# item_2223_Frontend.net
KiCad netlist of a schematic drawn in EAGLE
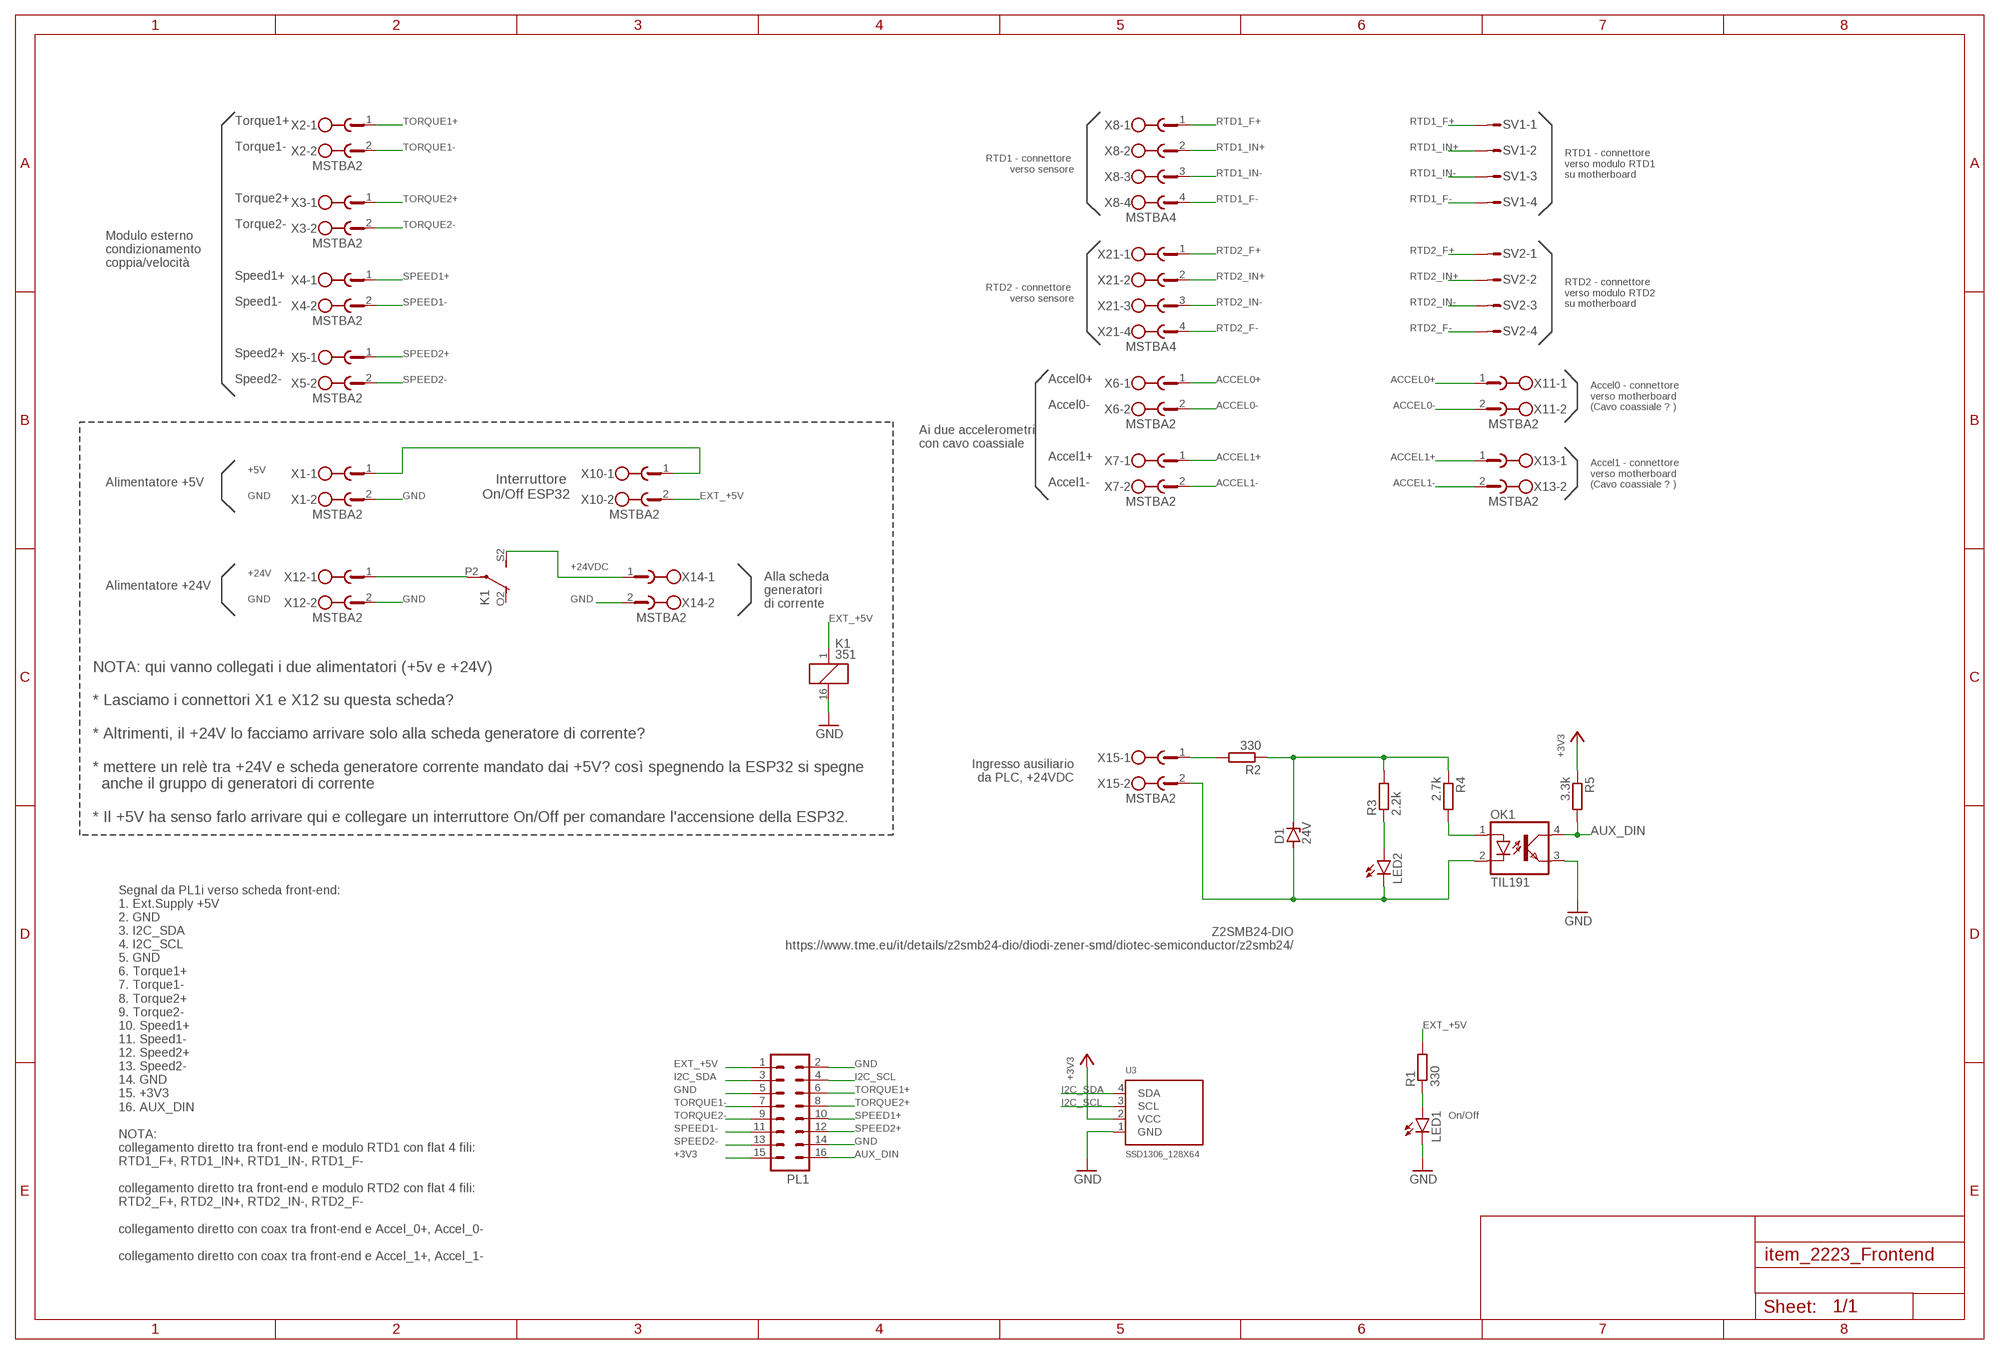
[diagram p0: schematic, sheet 1]

(export (version "E")
  (design (tool "Eeschema 10.0.6"))
  (components
    (comp (ref "D1")
      (value "24V")
      (footprint "eagle-import:SMB")
      (libsource (lib "eagle-import") (part "ZENER-DIODESMB"))
    )
    (comp (ref "K1")
      (value "351")
      (footprint "eagle-import:351")
      (libsource (lib "eagle-import") (part "351"))
    )
    (comp (ref "LED1")
      (value "LED5MM")
      (footprint "eagle-import:LED5MM")
      (libsource (lib "eagle-import") (part "LED5MM"))
    )
    (comp (ref "LED2")
      (value "LED5MM")
      (footprint "eagle-import:LED5MM")
      (libsource (lib "eagle-import") (part "LED5MM"))
    )
    (comp (ref "OK1")
      (value "TIL191")
      (footprint "eagle-import:DIL04")
      (libsource (lib "eagle-import") (part "TIL191"))
    )
    (comp (ref "PL1")
      (value "16H")
      (footprint "eagle-import:16H")
      (libsource (lib "eagle-import") (part "16H"))
    )
    (comp (ref "R1")
      (value "330")
      (footprint "eagle-import:R0805")
      (libsource (lib "eagle-import") (part "R-EU_R0805"))
    )
    (comp (ref "R2")
      (value "330")
      (footprint "eagle-import:R0805")
      (libsource (lib "eagle-import") (part "R-EU_R0805"))
    )
    (comp (ref "R3")
      (value "2.2k")
      (footprint "eagle-import:R0805")
      (libsource (lib "eagle-import") (part "R-EU_R0805"))
    )
    (comp (ref "R4")
      (value "2.7k")
      (footprint "eagle-import:R0805")
      (libsource (lib "eagle-import") (part "R-EU_R0805"))
    )
    (comp (ref "R5")
      (value "3.3k")
      (footprint "eagle-import:R0805")
      (libsource (lib "eagle-import") (part "R-EU_R0805"))
    )
    (comp (ref "SV1")
      (value "S04P")
      (footprint "eagle-import:S04P")
      (libsource (lib "eagle-import") (part "S04P"))
    )
    (comp (ref "SV2")
      (value "S04P")
      (footprint "eagle-import:S04P")
      (libsource (lib "eagle-import") (part "S04P"))
    )
    (comp (ref "U3")
      (value "SSD1306_128X64")
      (footprint "eagle-import:128X64")
      (libsource (lib "eagle-import") (part "SSD1306_128X64"))
    )
    (comp (ref "X1")
      (value "MSTBA2")
      (footprint "eagle-import:MSTBA2")
      (fields (field (name "MF") "FARNELL") (field (name "MPN") "1757242"))
      (libsource (lib "eagle-import") (part "MSTBA2"))
    )
    (comp (ref "X2")
      (value "MSTBA2")
      (footprint "eagle-import:MSTBA2")
      (fields (field (name "MF") "FARNELL") (field (name "MPN") "1757242"))
      (libsource (lib "eagle-import") (part "MSTBA2"))
    )
    (comp (ref "X3")
      (value "MSTBA2")
      (footprint "eagle-import:MSTBA2")
      (fields (field (name "MF") "FARNELL") (field (name "MPN") "1757242"))
      (libsource (lib "eagle-import") (part "MSTBA2"))
    )
    (comp (ref "X4")
      (value "MSTBA2")
      (footprint "eagle-import:MSTBA2")
      (fields (field (name "MF") "FARNELL") (field (name "MPN") "1757242"))
      (libsource (lib "eagle-import") (part "MSTBA2"))
    )
    (comp (ref "X5")
      (value "MSTBA2")
      (footprint "eagle-import:MSTBA2")
      (fields (field (name "MF") "FARNELL") (field (name "MPN") "1757242"))
      (libsource (lib "eagle-import") (part "MSTBA2"))
    )
    (comp (ref "X6")
      (value "MSTBA2")
      (footprint "eagle-import:MSTBA2")
      (fields (field (name "MF") "FARNELL") (field (name "MPN") "1757242"))
      (libsource (lib "eagle-import") (part "MSTBA2"))
    )
    (comp (ref "X7")
      (value "MSTBA2")
      (footprint "eagle-import:MSTBA2")
      (fields (field (name "MF") "FARNELL") (field (name "MPN") "1757242"))
      (libsource (lib "eagle-import") (part "MSTBA2"))
    )
    (comp (ref "X8")
      (value "MSTBA4")
      (footprint "eagle-import:MSTBA4")
      (fields (field (name "MF") "FARNELL") (field (name "MPN") "1757268"))
      (libsource (lib "eagle-import") (part "MSTBA4"))
    )
    (comp (ref "X10")
      (value "MSTBA2")
      (footprint "eagle-import:MSTBA2")
      (fields (field (name "MF") "FARNELL") (field (name "MPN") "1757242"))
      (libsource (lib "eagle-import") (part "MSTBA2"))
    )
    (comp (ref "X11")
      (value "MSTBA2")
      (footprint "eagle-import:MSTBA2")
      (fields (field (name "MF") "FARNELL") (field (name "MPN") "1757242"))
      (libsource (lib "eagle-import") (part "MSTBA2"))
    )
    (comp (ref "X12")
      (value "MSTBA2")
      (footprint "eagle-import:MSTBA2")
      (fields (field (name "MF") "FARNELL") (field (name "MPN") "1757242"))
      (libsource (lib "eagle-import") (part "MSTBA2"))
    )
    (comp (ref "X13")
      (value "MSTBA2")
      (footprint "eagle-import:MSTBA2")
      (fields (field (name "MF") "FARNELL") (field (name "MPN") "1757242"))
      (libsource (lib "eagle-import") (part "MSTBA2"))
    )
    (comp (ref "X14")
      (value "MSTBA2")
      (footprint "eagle-import:MSTBA2")
      (fields (field (name "MF") "FARNELL") (field (name "MPN") "1757242"))
      (libsource (lib "eagle-import") (part "MSTBA2"))
    )
    (comp (ref "X15")
      (value "MSTBA2")
      (footprint "eagle-import:MSTBA2")
      (fields (field (name "MF") "FARNELL") (field (name "MPN") "1757242"))
      (libsource (lib "eagle-import") (part "MSTBA2"))
    )
    (comp (ref "X21")
      (value "MSTBA4")
      (footprint "eagle-import:MSTBA4")
      (fields (field (name "MF") "FARNELL") (field (name "MPN") "1757268"))
      (libsource (lib "eagle-import") (part "MSTBA4"))
    )
  )
  (nets
    (net (code "1") (name "+3V3") (class "Default")
      (node (ref "PL1") (pin "15") (pinfunction "15_15") (pintype "passive"))
      (node (ref "R5") (pin "1") (pinfunction "1_1") (pintype "passive"))
      (node (ref "U3") (pin "2") (pinfunction "VCC_2") (pintype "power_in"))
    )
    (net (code "2") (name "/+24VDC") (class "Default")
      (node (ref "K1") (pin "S2") (pinfunction "S_S2") (pintype "passive"))
      (node (ref "X14") (pin "1") (pinfunction "1_1") (pintype "passive"))
    )
    (net (code "3") (name "/ACCEL0+") (class "Default")
      (node (ref "X11") (pin "1") (pinfunction "1_1") (pintype "passive"))
      (node (ref "X6") (pin "1") (pinfunction "1_1") (pintype "passive"))
    )
    (net (code "4") (name "/ACCEL0-") (class "Default")
      (node (ref "X11") (pin "2") (pinfunction "1_2") (pintype "passive"))
      (node (ref "X6") (pin "2") (pinfunction "1_2") (pintype "passive"))
    )
    (net (code "5") (name "/ACCEL1+") (class "Default")
      (node (ref "X13") (pin "1") (pinfunction "1_1") (pintype "passive"))
      (node (ref "X7") (pin "1") (pinfunction "1_1") (pintype "passive"))
    )
    (net (code "6") (name "/ACCEL1-") (class "Default")
      (node (ref "X13") (pin "2") (pinfunction "1_2") (pintype "passive"))
      (node (ref "X7") (pin "2") (pinfunction "1_2") (pintype "passive"))
    )
    (net (code "7") (name "/AUX_DIN") (class "Default")
      (node (ref "OK1") (pin "4") (pinfunction "COL_4") (pintype "passive"))
      (node (ref "PL1") (pin "16") (pinfunction "16_16") (pintype "passive"))
      (node (ref "R5") (pin "2") (pinfunction "2_2") (pintype "passive"))
    )
    (net (code "8") (name "/EXT_+5V") (class "Default")
      (node (ref "K1") (pin "1") (pinfunction "1_1") (pintype "passive"))
      (node (ref "PL1") (pin "1") (pinfunction "1_1") (pintype "passive"))
      (node (ref "R1") (pin "2") (pinfunction "2_2") (pintype "passive"))
      (node (ref "X10") (pin "2") (pinfunction "1_2") (pintype "passive"))
    )
    (net (code "9") (name "/I2C_SCL") (class "Default")
      (node (ref "PL1") (pin "4") (pinfunction "4_4") (pintype "passive"))
      (node (ref "U3") (pin "3") (pinfunction "SCL_3") (pintype "bidirectional"))
    )
    (net (code "10") (name "/I2C_SDA") (class "Default")
      (node (ref "PL1") (pin "3") (pinfunction "3_3") (pintype "passive"))
      (node (ref "U3") (pin "4") (pinfunction "SDA_4") (pintype "bidirectional"))
    )
    (net (code "11") (name "/RTD1_F+") (class "Default")
      (node (ref "SV1") (pin "1") (pinfunction "S_1") (pintype "passive"))
      (node (ref "X8") (pin "1") (pinfunction "1_1") (pintype "passive"))
    )
    (net (code "12") (name "/RTD1_F-") (class "Default")
      (node (ref "SV1") (pin "4") (pinfunction "S_4") (pintype "passive"))
      (node (ref "X8") (pin "4") (pinfunction "1_4") (pintype "passive"))
    )
    (net (code "13") (name "/RTD1_IN+") (class "Default")
      (node (ref "SV1") (pin "2") (pinfunction "S_2") (pintype "passive"))
      (node (ref "X8") (pin "2") (pinfunction "1_2") (pintype "passive"))
    )
    (net (code "14") (name "/RTD1_IN-") (class "Default")
      (node (ref "SV1") (pin "3") (pinfunction "S_3") (pintype "passive"))
      (node (ref "X8") (pin "3") (pinfunction "1_3") (pintype "passive"))
    )
    (net (code "15") (name "/RTD2_F+") (class "Default")
      (node (ref "SV2") (pin "1") (pinfunction "S_1") (pintype "passive"))
      (node (ref "X21") (pin "1") (pinfunction "1_1") (pintype "passive"))
    )
    (net (code "16") (name "/RTD2_F-") (class "Default")
      (node (ref "SV2") (pin "4") (pinfunction "S_4") (pintype "passive"))
      (node (ref "X21") (pin "4") (pinfunction "1_4") (pintype "passive"))
    )
    (net (code "17") (name "/RTD2_IN+") (class "Default")
      (node (ref "SV2") (pin "2") (pinfunction "S_2") (pintype "passive"))
      (node (ref "X21") (pin "2") (pinfunction "1_2") (pintype "passive"))
    )
    (net (code "18") (name "/RTD2_IN-") (class "Default")
      (node (ref "SV2") (pin "3") (pinfunction "S_3") (pintype "passive"))
      (node (ref "X21") (pin "3") (pinfunction "1_3") (pintype "passive"))
    )
    (net (code "19") (name "/SPEED1+") (class "Default")
      (node (ref "PL1") (pin "10") (pinfunction "10_10") (pintype "passive"))
      (node (ref "X4") (pin "1") (pinfunction "1_1") (pintype "passive"))
    )
    (net (code "20") (name "/SPEED1-") (class "Default")
      (node (ref "PL1") (pin "11") (pinfunction "11_11") (pintype "passive"))
      (node (ref "X4") (pin "2") (pinfunction "1_2") (pintype "passive"))
    )
    (net (code "21") (name "/SPEED2+") (class "Default")
      (node (ref "PL1") (pin "12") (pinfunction "12_12") (pintype "passive"))
      (node (ref "X5") (pin "1") (pinfunction "1_1") (pintype "passive"))
    )
    (net (code "22") (name "/SPEED2-") (class "Default")
      (node (ref "PL1") (pin "13") (pinfunction "13_13") (pintype "passive"))
      (node (ref "X5") (pin "2") (pinfunction "1_2") (pintype "passive"))
    )
    (net (code "23") (name "/TORQUE1+") (class "Default")
      (node (ref "PL1") (pin "6") (pinfunction "6_6") (pintype "passive"))
      (node (ref "X2") (pin "1") (pinfunction "1_1") (pintype "passive"))
    )
    (net (code "24") (name "/TORQUE1-") (class "Default")
      (node (ref "PL1") (pin "7") (pinfunction "7_7") (pintype "passive"))
      (node (ref "X2") (pin "2") (pinfunction "1_2") (pintype "passive"))
    )
    (net (code "25") (name "/TORQUE2+") (class "Default")
      (node (ref "PL1") (pin "8") (pinfunction "8_8") (pintype "passive"))
      (node (ref "X3") (pin "1") (pinfunction "1_1") (pintype "passive"))
    )
    (net (code "26") (name "/TORQUE2-") (class "Default")
      (node (ref "PL1") (pin "9") (pinfunction "9_9") (pintype "passive"))
      (node (ref "X3") (pin "2") (pinfunction "1_2") (pintype "passive"))
    )
    (net (code "27") (name "GND") (class "Default")
      (node (ref "K1") (pin "16") (pinfunction "2_16") (pintype "passive"))
      (node (ref "LED1") (pin "K") (pinfunction "C_K") (pintype "passive"))
      (node (ref "OK1") (pin "3") (pinfunction "EMIT_3") (pintype "passive"))
      (node (ref "PL1") (pin "14") (pinfunction "14_14") (pintype "passive"))
      (node (ref "PL1") (pin "2") (pinfunction "2_2") (pintype "passive"))
      (node (ref "PL1") (pin "5") (pinfunction "5_5") (pintype "passive"))
      (node (ref "U3") (pin "1") (pinfunction "GND_1") (pintype "power_in"))
      (node (ref "X1") (pin "2") (pinfunction "1_2") (pintype "passive"))
      (node (ref "X12") (pin "2") (pinfunction "1_2") (pintype "passive"))
      (node (ref "X14") (pin "2") (pinfunction "1_2") (pintype "passive"))
    )
    (net (code "28") (name "Net-(D1-PadC)") (class "Default")
      (node (ref "D1") (pin "C") (pinfunction "C_C") (pintype "passive"))
      (node (ref "R2") (pin "1") (pinfunction "1_1") (pintype "passive"))
      (node (ref "R3") (pin "2") (pinfunction "2_2") (pintype "passive"))
      (node (ref "R4") (pin "1") (pinfunction "1_1") (pintype "passive"))
    )
    (net (code "29") (name "Net-(K1C-P)") (class "Default")
      (node (ref "K1") (pin "P2") (pinfunction "P_P2") (pintype "passive"))
      (node (ref "X12") (pin "1") (pinfunction "1_1") (pintype "passive"))
    )
    (net (code "30") (name "Net-(LED1-PadA)") (class "Default")
      (node (ref "LED1") (pin "A") (pinfunction "A_A") (pintype "passive"))
      (node (ref "R1") (pin "1") (pinfunction "1_1") (pintype "passive"))
    )
    (net (code "31") (name "Net-(LED2-C)") (class "Default")
      (node (ref "D1") (pin "A") (pinfunction "A_A") (pintype "passive"))
      (node (ref "LED2") (pin "K") (pinfunction "C_K") (pintype "passive"))
      (node (ref "OK1") (pin "2") (pinfunction "C_2") (pintype "passive"))
      (node (ref "X15") (pin "2") (pinfunction "1_2") (pintype "passive"))
    )
    (net (code "32") (name "Net-(LED2-PadA)") (class "Default")
      (node (ref "LED2") (pin "A") (pinfunction "A_A") (pintype "passive"))
      (node (ref "R3") (pin "1") (pinfunction "1_1") (pintype "passive"))
    )
    (net (code "33") (name "Net-(OK1-A)") (class "Default")
      (node (ref "OK1") (pin "1") (pinfunction "A_1") (pintype "passive"))
      (node (ref "R4") (pin "2") (pinfunction "2_2") (pintype "passive"))
    )
    (net (code "34") (name "Net-(R2-Pad2)") (class "Default")
      (node (ref "R2") (pin "2") (pinfunction "2_2") (pintype "passive"))
      (node (ref "X15") (pin "1") (pinfunction "1_1") (pintype "passive"))
    )
    (net (code "35") (name "Net-(X1-Pad1)") (class "Default")
      (node (ref "X1") (pin "1") (pinfunction "1_1") (pintype "passive"))
      (node (ref "X10") (pin "1") (pinfunction "1_1") (pintype "passive"))
    )
    (net (code "36") (name "unconnected-(K1C-O-PadO2)") (class "Default")
      (node (ref "K1") (pin "O2") (pinfunction "O_O2") (pintype "passive"))
    )
  )
)
